# usb_blaster_rev_a.net
KiCad netlist of a schematic drawn in EAGLE
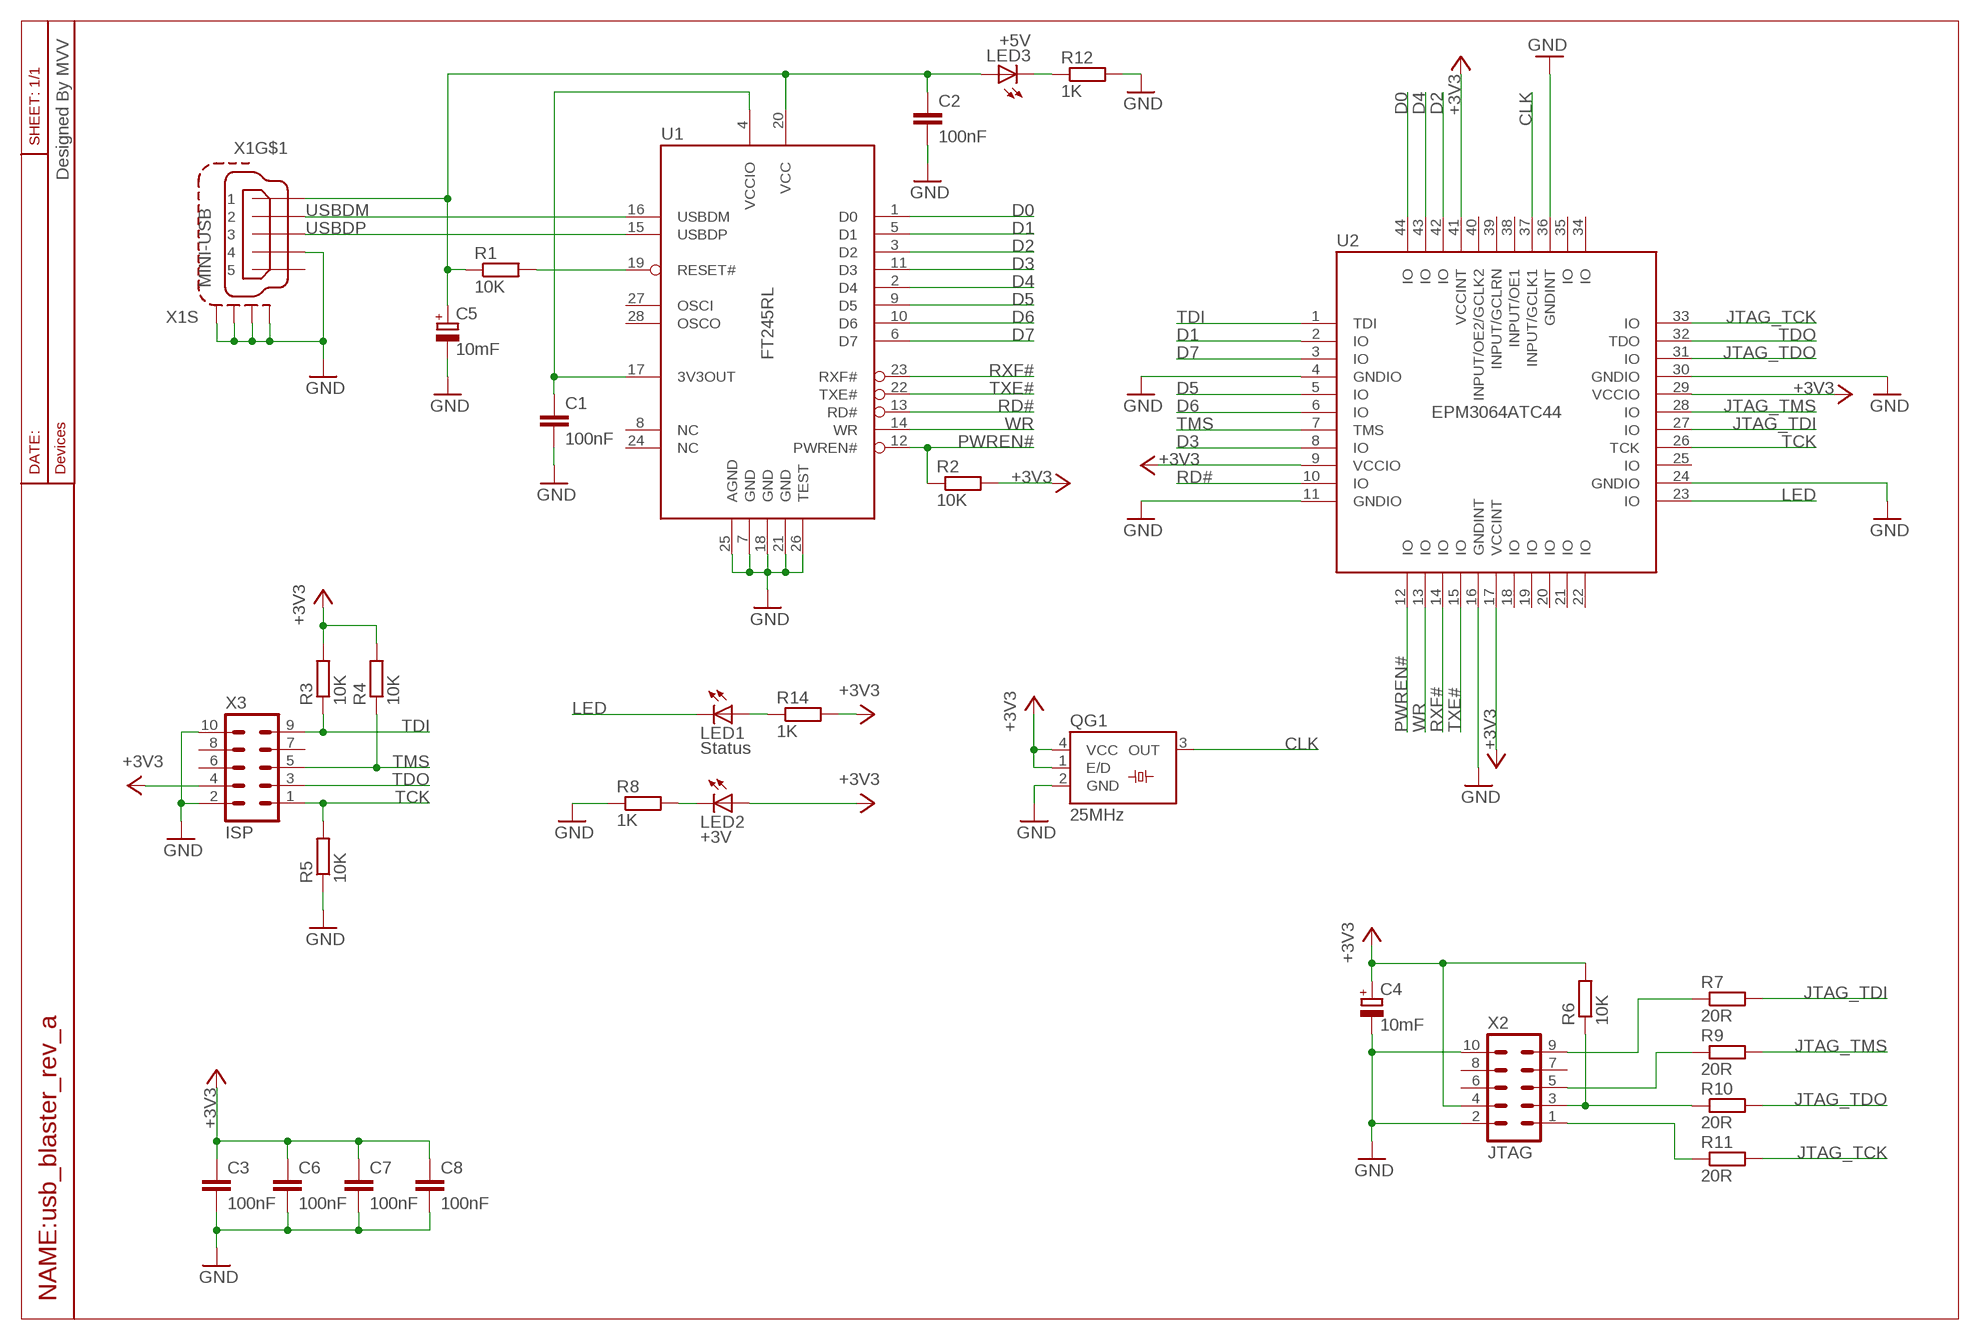
[diagram p0: schematic, sheet 1]

(export (version "E")
  (design (tool "Eeschema 10.0.6"))
  (components
    (comp (ref "C1")
      (value "100nF")
      (footprint "eagle-import:C0805")
      (libsource (lib "eagle-import") (part "C-EUC0805"))
    )
    (comp (ref "C2")
      (value "100nF")
      (footprint "eagle-import:C0805")
      (libsource (lib "eagle-import") (part "C-EUC0805"))
    )
    (comp (ref "C3")
      (value "100nF")
      (footprint "eagle-import:C0805")
      (libsource (lib "eagle-import") (part "C-EUC0805"))
    )
    (comp (ref "C4")
      (value "10mF")
      (footprint "eagle-import:CT6032")
      (libsource (lib "eagle-import") (part "CPOL-EUCT6032"))
    )
    (comp (ref "C5")
      (value "10mF")
      (footprint "eagle-import:CT6032")
      (libsource (lib "eagle-import") (part "CPOL-EUCT6032"))
    )
    (comp (ref "C6")
      (value "100nF")
      (footprint "eagle-import:C0805")
      (libsource (lib "eagle-import") (part "C-EUC0805"))
    )
    (comp (ref "C7")
      (value "100nF")
      (footprint "eagle-import:C0805")
      (libsource (lib "eagle-import") (part "C-EUC0805"))
    )
    (comp (ref "C8")
      (value "100nF")
      (footprint "eagle-import:C0805")
      (libsource (lib "eagle-import") (part "C-EUC0805"))
    )
    (comp (ref "LED1")
      (value "Status")
      (footprint "eagle-import:LED3MM")
      (libsource (lib "eagle-import") (part "LED3MM"))
    )
    (comp (ref "LED2")
      (value "+3V")
      (footprint "eagle-import:LED3MM")
      (libsource (lib "eagle-import") (part "LED3MM"))
    )
    (comp (ref "LED3")
      (value "+5V")
      (footprint "eagle-import:LED3MM")
      (libsource (lib "eagle-import") (part "LED3MM"))
    )
    (comp (ref "QG1")
      (value "25MHz")
      (footprint "eagle-import:SM77H")
      (libsource (lib "eagle-import") (part "SM77H"))
    )
    (comp (ref "R1")
      (value "10K")
      (footprint "eagle-import:R0805")
      (libsource (lib "eagle-import") (part "R-EU_R0805"))
    )
    (comp (ref "R2")
      (value "10K")
      (footprint "eagle-import:R0805")
      (libsource (lib "eagle-import") (part "R-EU_R0805"))
    )
    (comp (ref "R3")
      (value "10K")
      (footprint "eagle-import:R0805")
      (libsource (lib "eagle-import") (part "R-EU_R0805"))
    )
    (comp (ref "R4")
      (value "10K")
      (footprint "eagle-import:R0805")
      (libsource (lib "eagle-import") (part "R-EU_R0805"))
    )
    (comp (ref "R5")
      (value "10K")
      (footprint "eagle-import:R0805")
      (libsource (lib "eagle-import") (part "R-EU_R0805"))
    )
    (comp (ref "R6")
      (value "10K")
      (footprint "eagle-import:R0805")
      (libsource (lib "eagle-import") (part "R-EU_R0805"))
    )
    (comp (ref "R7")
      (value "20R")
      (footprint "eagle-import:R0805")
      (libsource (lib "eagle-import") (part "R-EU_R0805"))
    )
    (comp (ref "R8")
      (value "1K")
      (footprint "eagle-import:R0805")
      (libsource (lib "eagle-import") (part "R-EU_R0805"))
    )
    (comp (ref "R9")
      (value "20R")
      (footprint "eagle-import:R0805")
      (libsource (lib "eagle-import") (part "R-EU_R0805"))
    )
    (comp (ref "R10")
      (value "20R")
      (footprint "eagle-import:R0805")
      (libsource (lib "eagle-import") (part "R-EU_R0805"))
    )
    (comp (ref "R11")
      (value "20R")
      (footprint "eagle-import:R0805")
      (libsource (lib "eagle-import") (part "R-EU_R0805"))
    )
    (comp (ref "R12")
      (value "1K")
      (footprint "eagle-import:R0805")
      (libsource (lib "eagle-import") (part "R-EU_R0805"))
    )
    (comp (ref "R14")
      (value "1K")
      (footprint "eagle-import:R0805")
      (libsource (lib "eagle-import") (part "R-EU_R0805"))
    )
    (comp (ref "U1")
      (value "FT245RL")
      (footprint "eagle-import:SSOP28")
      (libsource (lib "eagle-import") (part "FT245RL"))
    )
    (comp (ref "U2")
      (value "EPM3064ATC44")
      (footprint "eagle-import:TQFP44")
      (libsource (lib "eagle-import") (part "EPM3064ATC44"))
    )
    (comp (ref "X1")
      (value "MINI-USB")
      (footprint "eagle-import:32005-201")
      (libsource (lib "eagle-import") (part "MINI-USB-SCHIELD-32005-201"))
    )
    (comp (ref "X2")
      (value "JTAG")
      (footprint "eagle-import:ML10")
      (libsource (lib "eagle-import") (part "ML10"))
    )
    (comp (ref "X3")
      (value "ISP")
      (footprint "eagle-import:MA05-2")
      (libsource (lib "eagle-import") (part "MA05-2"))
    )
  )
  (nets
    (net (code "1") (name "+3V3") (class "Default")
      (node (ref "C3") (pin "1") (pinfunction "1_1") (pintype "passive"))
      (node (ref "C4") (pin "+") (pinfunction "+_+") (pintype "passive"))
      (node (ref "C6") (pin "1") (pinfunction "1_1") (pintype "passive"))
      (node (ref "C7") (pin "1") (pinfunction "1_1") (pintype "passive"))
      (node (ref "C8") (pin "1") (pinfunction "1_1") (pintype "passive"))
      (node (ref "LED2") (pin "A") (pinfunction "A_A") (pintype "passive"))
      (node (ref "QG1") (pin "1") (pinfunction "E/D_1") (pintype "input"))
      (node (ref "QG1") (pin "4") (pinfunction "VCC_4") (pintype "power_in"))
      (node (ref "R14") (pin "2") (pinfunction "2_2") (pintype "passive"))
      (node (ref "R2") (pin "2") (pinfunction "2_2") (pintype "passive"))
      (node (ref "R3") (pin "2") (pinfunction "2_2") (pintype "passive"))
      (node (ref "R4") (pin "2") (pinfunction "2_2") (pintype "passive"))
      (node (ref "R6") (pin "2") (pinfunction "2_2") (pintype "passive"))
      (node (ref "U2") (pin "17") (pinfunction "VCCINT_17") (pintype "power_in"))
      (node (ref "U2") (pin "29") (pinfunction "VCCIO_29") (pintype "power_in"))
      (node (ref "U2") (pin "41") (pinfunction "VCCINT_41") (pintype "power_in"))
      (node (ref "U2") (pin "9") (pinfunction "VCCIO_9") (pintype "power_in"))
      (node (ref "X2") (pin "4") (pinfunction "4_4") (pintype "passive"))
      (node (ref "X3") (pin "4") (pinfunction "4_4") (pintype "passive"))
    )
    (net (code "2") (name "/CLK") (class "Default")
      (node (ref "QG1") (pin "3") (pinfunction "OUT_3") (pintype "output"))
      (node (ref "U2") (pin "37") (pinfunction "INPUT/GCLK1_37") (pintype "input"))
    )
    (net (code "3") (name "/D0") (class "Default")
      (node (ref "U1") (pin "1") (pinfunction "D0_1") (pintype "bidirectional"))
      (node (ref "U2") (pin "44") (pinfunction "IO_44") (pintype "bidirectional"))
    )
    (net (code "4") (name "/D1") (class "Default")
      (node (ref "U1") (pin "5") (pinfunction "D1_5") (pintype "bidirectional"))
      (node (ref "U2") (pin "2") (pinfunction "IO_2") (pintype "bidirectional"))
    )
    (net (code "5") (name "/D2") (class "Default")
      (node (ref "U1") (pin "3") (pinfunction "D2_3") (pintype "bidirectional"))
      (node (ref "U2") (pin "42") (pinfunction "IO_42") (pintype "bidirectional"))
    )
    (net (code "6") (name "/D3") (class "Default")
      (node (ref "U1") (pin "11") (pinfunction "D3_11") (pintype "bidirectional"))
      (node (ref "U2") (pin "8") (pinfunction "IO_8") (pintype "bidirectional"))
    )
    (net (code "7") (name "/D4") (class "Default")
      (node (ref "U1") (pin "2") (pinfunction "D4_2") (pintype "bidirectional"))
      (node (ref "U2") (pin "43") (pinfunction "IO_43") (pintype "bidirectional"))
    )
    (net (code "8") (name "/D5") (class "Default")
      (node (ref "U1") (pin "9") (pinfunction "D5_9") (pintype "bidirectional"))
      (node (ref "U2") (pin "5") (pinfunction "IO_5") (pintype "bidirectional"))
    )
    (net (code "9") (name "/D6") (class "Default")
      (node (ref "U1") (pin "10") (pinfunction "D6_10") (pintype "bidirectional"))
      (node (ref "U2") (pin "6") (pinfunction "IO_6") (pintype "bidirectional"))
    )
    (net (code "10") (name "/D7") (class "Default")
      (node (ref "U1") (pin "6") (pinfunction "D7_6") (pintype "bidirectional"))
      (node (ref "U2") (pin "3") (pinfunction "IO_3") (pintype "bidirectional"))
    )
    (net (code "11") (name "/JTAG_TCK") (class "Default")
      (node (ref "R11") (pin "2") (pinfunction "2_2") (pintype "passive"))
      (node (ref "U2") (pin "33") (pinfunction "IO_33") (pintype "bidirectional"))
    )
    (net (code "12") (name "/JTAG_TDI") (class "Default")
      (node (ref "R7") (pin "2") (pinfunction "2_2") (pintype "passive"))
      (node (ref "U2") (pin "27") (pinfunction "IO_27") (pintype "bidirectional"))
    )
    (net (code "13") (name "/JTAG_TDO") (class "Default")
      (node (ref "R10") (pin "2") (pinfunction "2_2") (pintype "passive"))
      (node (ref "U2") (pin "31") (pinfunction "IO_31") (pintype "bidirectional"))
    )
    (net (code "14") (name "/JTAG_TMS") (class "Default")
      (node (ref "R9") (pin "2") (pinfunction "2_2") (pintype "passive"))
      (node (ref "U2") (pin "28") (pinfunction "IO_28") (pintype "bidirectional"))
    )
    (net (code "15") (name "/LED") (class "Default")
      (node (ref "LED1") (pin "K") (pinfunction "C_K") (pintype "passive"))
      (node (ref "U2") (pin "23") (pinfunction "IO_23") (pintype "bidirectional"))
    )
    (net (code "16") (name "/PWREN#") (class "Default")
      (node (ref "R2") (pin "1") (pinfunction "1_1") (pintype "passive"))
      (node (ref "U1") (pin "12") (pinfunction "PWREN#_12") (pintype "output"))
      (node (ref "U2") (pin "12") (pinfunction "IO_12") (pintype "bidirectional"))
    )
    (net (code "17") (name "/RD#") (class "Default")
      (node (ref "U1") (pin "13") (pinfunction "RD#_13") (pintype "input"))
      (node (ref "U2") (pin "10") (pinfunction "IO_10") (pintype "bidirectional"))
    )
    (net (code "18") (name "/RXF#") (class "Default")
      (node (ref "U1") (pin "23") (pinfunction "RXF#_23") (pintype "output"))
      (node (ref "U2") (pin "14") (pinfunction "IO_14") (pintype "bidirectional"))
    )
    (net (code "19") (name "/TCK") (class "Default")
      (node (ref "R5") (pin "2") (pinfunction "2_2") (pintype "passive"))
      (node (ref "U2") (pin "26") (pinfunction "TCK_26") (pintype "input"))
      (node (ref "X3") (pin "1") (pinfunction "1_1") (pintype "passive"))
    )
    (net (code "20") (name "/TDI") (class "Default")
      (node (ref "R3") (pin "1") (pinfunction "1_1") (pintype "passive"))
      (node (ref "U2") (pin "1") (pinfunction "TDI_1") (pintype "input"))
      (node (ref "X3") (pin "9") (pinfunction "9_9") (pintype "passive"))
    )
    (net (code "21") (name "/TDO") (class "Default")
      (node (ref "U2") (pin "32") (pinfunction "TDO_32") (pintype "output"))
      (node (ref "X3") (pin "3") (pinfunction "3_3") (pintype "passive"))
    )
    (net (code "22") (name "/TMS") (class "Default")
      (node (ref "R4") (pin "1") (pinfunction "1_1") (pintype "passive"))
      (node (ref "U2") (pin "7") (pinfunction "TMS_7") (pintype "input"))
      (node (ref "X3") (pin "5") (pinfunction "5_5") (pintype "passive"))
    )
    (net (code "23") (name "/TXE#") (class "Default")
      (node (ref "U1") (pin "22") (pinfunction "TXE#_22") (pintype "output"))
      (node (ref "U2") (pin "15") (pinfunction "IO_15") (pintype "bidirectional"))
    )
    (net (code "24") (name "/USBDM") (class "Default")
      (node (ref "U1") (pin "16") (pinfunction "USBDM_16") (pintype "bidirectional"))
      (node (ref "X1") (pin "2") (pinfunction "2_2") (pintype "passive"))
    )
    (net (code "25") (name "/USBDP") (class "Default")
      (node (ref "U1") (pin "15") (pinfunction "USBDP_15") (pintype "bidirectional"))
      (node (ref "X1") (pin "3") (pinfunction "3_3") (pintype "passive"))
    )
    (net (code "26") (name "/WR") (class "Default")
      (node (ref "U1") (pin "14") (pinfunction "WR_14") (pintype "input"))
      (node (ref "U2") (pin "13") (pinfunction "IO_13") (pintype "bidirectional"))
    )
    (net (code "27") (name "GND") (class "Default")
      (node (ref "C1") (pin "2") (pinfunction "2_2") (pintype "passive"))
      (node (ref "C2") (pin "2") (pinfunction "2_2") (pintype "passive"))
      (node (ref "C3") (pin "2") (pinfunction "2_2") (pintype "passive"))
      (node (ref "C4") (pin "-") (pinfunction "-_-") (pintype "passive"))
      (node (ref "C5") (pin "-") (pinfunction "-_-") (pintype "passive"))
      (node (ref "C6") (pin "2") (pinfunction "2_2") (pintype "passive"))
      (node (ref "C7") (pin "2") (pinfunction "2_2") (pintype "passive"))
      (node (ref "C8") (pin "2") (pinfunction "2_2") (pintype "passive"))
      (node (ref "QG1") (pin "2") (pinfunction "GND_2") (pintype "power_in"))
      (node (ref "R12") (pin "2") (pinfunction "2_2") (pintype "passive"))
      (node (ref "R5") (pin "1") (pinfunction "1_1") (pintype "passive"))
      (node (ref "R8") (pin "1") (pinfunction "1_1") (pintype "passive"))
      (node (ref "U1") (pin "18") (pinfunction "GND_18") (pintype "power_in"))
      (node (ref "U1") (pin "21") (pinfunction "GND_21") (pintype "power_in"))
      (node (ref "U1") (pin "25") (pinfunction "AGND_25") (pintype "power_in"))
      (node (ref "U1") (pin "26") (pinfunction "TEST_26") (pintype "input"))
      (node (ref "U1") (pin "7") (pinfunction "GND_7") (pintype "power_in"))
      (node (ref "U2") (pin "11") (pinfunction "GNDIO_11") (pintype "power_in"))
      (node (ref "U2") (pin "16") (pinfunction "GNDINT_16") (pintype "power_in"))
      (node (ref "U2") (pin "24") (pinfunction "GNDIO_24") (pintype "power_in"))
      (node (ref "U2") (pin "30") (pinfunction "GNDIO_30") (pintype "power_in"))
      (node (ref "U2") (pin "36") (pinfunction "GNDINT_36") (pintype "power_in"))
      (node (ref "U2") (pin "4") (pinfunction "GNDIO_4") (pintype "power_in"))
      (node (ref "X1") (pin "4") (pinfunction "4_4") (pintype "passive"))
      (node (ref "X1") (pin "M1") (pinfunction "S1_M1") (pintype "passive"))
      (node (ref "X1") (pin "M2") (pinfunction "S2_M2") (pintype "passive"))
      (node (ref "X1") (pin "M3") (pinfunction "S3_M3") (pintype "passive"))
      (node (ref "X1") (pin "M4") (pinfunction "S4_M4") (pintype "passive"))
      (node (ref "X2") (pin "10") (pinfunction "10_10") (pintype "passive"))
      (node (ref "X2") (pin "2") (pinfunction "2_2") (pintype "passive"))
      (node (ref "X3") (pin "10") (pinfunction "10_10") (pintype "passive"))
      (node (ref "X3") (pin "2") (pinfunction "2_2") (pintype "passive"))
    )
    (net (code "28") (name "Net-(LED1-PadA)") (class "Default")
      (node (ref "LED1") (pin "A") (pinfunction "A_A") (pintype "passive"))
      (node (ref "R14") (pin "1") (pinfunction "1_1") (pintype "passive"))
    )
    (net (code "29") (name "Net-(LED2-C)") (class "Default")
      (node (ref "LED2") (pin "K") (pinfunction "C_K") (pintype "passive"))
      (node (ref "R8") (pin "2") (pinfunction "2_2") (pintype "passive"))
    )
    (net (code "30") (name "Net-(LED3-C)") (class "Default")
      (node (ref "LED3") (pin "K") (pinfunction "C_K") (pintype "passive"))
      (node (ref "R12") (pin "1") (pinfunction "1_1") (pintype "passive"))
    )
    (net (code "31") (name "Net-(R7-Pad1)") (class "Default")
      (node (ref "R7") (pin "1") (pinfunction "1_1") (pintype "passive"))
      (node (ref "X2") (pin "9") (pinfunction "9_9") (pintype "passive"))
    )
    (net (code "32") (name "Net-(R9-Pad1)") (class "Default")
      (node (ref "R9") (pin "1") (pinfunction "1_1") (pintype "passive"))
      (node (ref "X2") (pin "5") (pinfunction "5_5") (pintype "passive"))
    )
    (net (code "33") (name "Net-(R10-Pad1)") (class "Default")
      (node (ref "R10") (pin "1") (pinfunction "1_1") (pintype "passive"))
      (node (ref "R6") (pin "1") (pinfunction "1_1") (pintype "passive"))
      (node (ref "X2") (pin "3") (pinfunction "3_3") (pintype "passive"))
    )
    (net (code "34") (name "Net-(R11-Pad1)") (class "Default")
      (node (ref "R11") (pin "1") (pinfunction "1_1") (pintype "passive"))
      (node (ref "X2") (pin "1") (pinfunction "1_1") (pintype "passive"))
    )
    (net (code "35") (name "Net-(U1-3V3OUT)") (class "Default")
      (node (ref "C1") (pin "1") (pinfunction "1_1") (pintype "passive"))
      (node (ref "U1") (pin "17") (pinfunction "3V3OUT_17") (pintype "output"))
      (node (ref "U1") (pin "4") (pinfunction "VCCIO_4") (pintype "power_in"))
    )
    (net (code "36") (name "Net-(U1-RESET#)") (class "Default")
      (node (ref "R1") (pin "2") (pinfunction "2_2") (pintype "passive"))
      (node (ref "U1") (pin "19") (pinfunction "RESET#_19") (pintype "input"))
    )
    (net (code "37") (name "Net-(U1-VCC)") (class "Default")
      (node (ref "C2") (pin "1") (pinfunction "1_1") (pintype "passive"))
      (node (ref "C5") (pin "+") (pinfunction "+_+") (pintype "passive"))
      (node (ref "LED3") (pin "A") (pinfunction "A_A") (pintype "passive"))
      (node (ref "R1") (pin "1") (pinfunction "1_1") (pintype "passive"))
      (node (ref "U1") (pin "20") (pinfunction "VCC_20") (pintype "power_in"))
      (node (ref "X1") (pin "1") (pinfunction "1_1") (pintype "passive"))
    )
    (net (code "38") (name "unconnected-(U1-NC-Pad8)") (class "Default")
      (node (ref "U1") (pin "8") (pinfunction "NC_8") (pintype "no_connect"))
    )
    (net (code "39") (name "unconnected-(U1-NC-Pad24)") (class "Default")
      (node (ref "U1") (pin "24") (pinfunction "NC_24") (pintype "no_connect"))
    )
    (net (code "40") (name "unconnected-(U1-OSCI-Pad27)") (class "Default")
      (node (ref "U1") (pin "27") (pinfunction "OSCI_27") (pintype "input"))
    )
    (net (code "41") (name "unconnected-(U1-OSCO-Pad28)") (class "Default")
      (node (ref "U1") (pin "28") (pinfunction "OSCO_28") (pintype "output"))
    )
    (net (code "42") (name "unconnected-(U2-INPUT{slash}GCLRN-Pad39)") (class "Default")
      (node (ref "U2") (pin "39") (pinfunction "INPUT/GCLRN_39") (pintype "input"))
    )
    (net (code "43") (name "unconnected-(U2-INPUT{slash}OE1-Pad38)") (class "Default")
      (node (ref "U2") (pin "38") (pinfunction "INPUT/OE1_38") (pintype "input"))
    )
    (net (code "44") (name "unconnected-(U2-INPUT{slash}OE2{slash}GCLK2-Pad40)") (class "Default")
      (node (ref "U2") (pin "40") (pinfunction "INPUT/OE2/GCLK2_40") (pintype "input"))
    )
    (net (code "45") (name "unconnected-(U2-IO-Pad18)") (class "Default")
      (node (ref "U2") (pin "18") (pinfunction "IO_18") (pintype "bidirectional"))
    )
    (net (code "46") (name "unconnected-(U2-IO-Pad19)") (class "Default")
      (node (ref "U2") (pin "19") (pinfunction "IO_19") (pintype "bidirectional"))
    )
    (net (code "47") (name "unconnected-(U2-IO-Pad20)") (class "Default")
      (node (ref "U2") (pin "20") (pinfunction "IO_20") (pintype "bidirectional"))
    )
    (net (code "48") (name "unconnected-(U2-IO-Pad21)") (class "Default")
      (node (ref "U2") (pin "21") (pinfunction "IO_21") (pintype "bidirectional"))
    )
    (net (code "49") (name "unconnected-(U2-IO-Pad22)") (class "Default")
      (node (ref "U2") (pin "22") (pinfunction "IO_22") (pintype "bidirectional"))
    )
    (net (code "50") (name "unconnected-(U2-IO-Pad25)") (class "Default")
      (node (ref "U2") (pin "25") (pinfunction "IO_25") (pintype "bidirectional"))
    )
    (net (code "51") (name "unconnected-(U2-IO-Pad34)") (class "Default")
      (node (ref "U2") (pin "34") (pinfunction "IO_34") (pintype "bidirectional"))
    )
    (net (code "52") (name "unconnected-(U2-IO-Pad35)") (class "Default")
      (node (ref "U2") (pin "35") (pinfunction "IO_35") (pintype "bidirectional"))
    )
    (net (code "53") (name "unconnected-(X1-Pad5)") (class "Default")
      (node (ref "X1") (pin "5") (pinfunction "5_5") (pintype "passive"))
    )
    (net (code "54") (name "unconnected-(X2-Pad6)") (class "Default")
      (node (ref "X2") (pin "6") (pinfunction "6_6") (pintype "passive"))
    )
    (net (code "55") (name "unconnected-(X2-Pad7)") (class "Default")
      (node (ref "X2") (pin "7") (pinfunction "7_7") (pintype "passive"))
    )
    (net (code "56") (name "unconnected-(X2-Pad8)") (class "Default")
      (node (ref "X2") (pin "8") (pinfunction "8_8") (pintype "passive"))
    )
    (net (code "57") (name "unconnected-(X3-Pad6)") (class "Default")
      (node (ref "X3") (pin "6") (pinfunction "6_6") (pintype "passive"))
    )
    (net (code "58") (name "unconnected-(X3-Pad7)") (class "Default")
      (node (ref "X3") (pin "7") (pinfunction "7_7") (pintype "passive"))
    )
    (net (code "59") (name "unconnected-(X3-Pad8)") (class "Default")
      (node (ref "X3") (pin "8") (pinfunction "8_8") (pintype "passive"))
    )
  )
)
